# led3.net
KiCad netlist of a schematic drawn in EAGLE
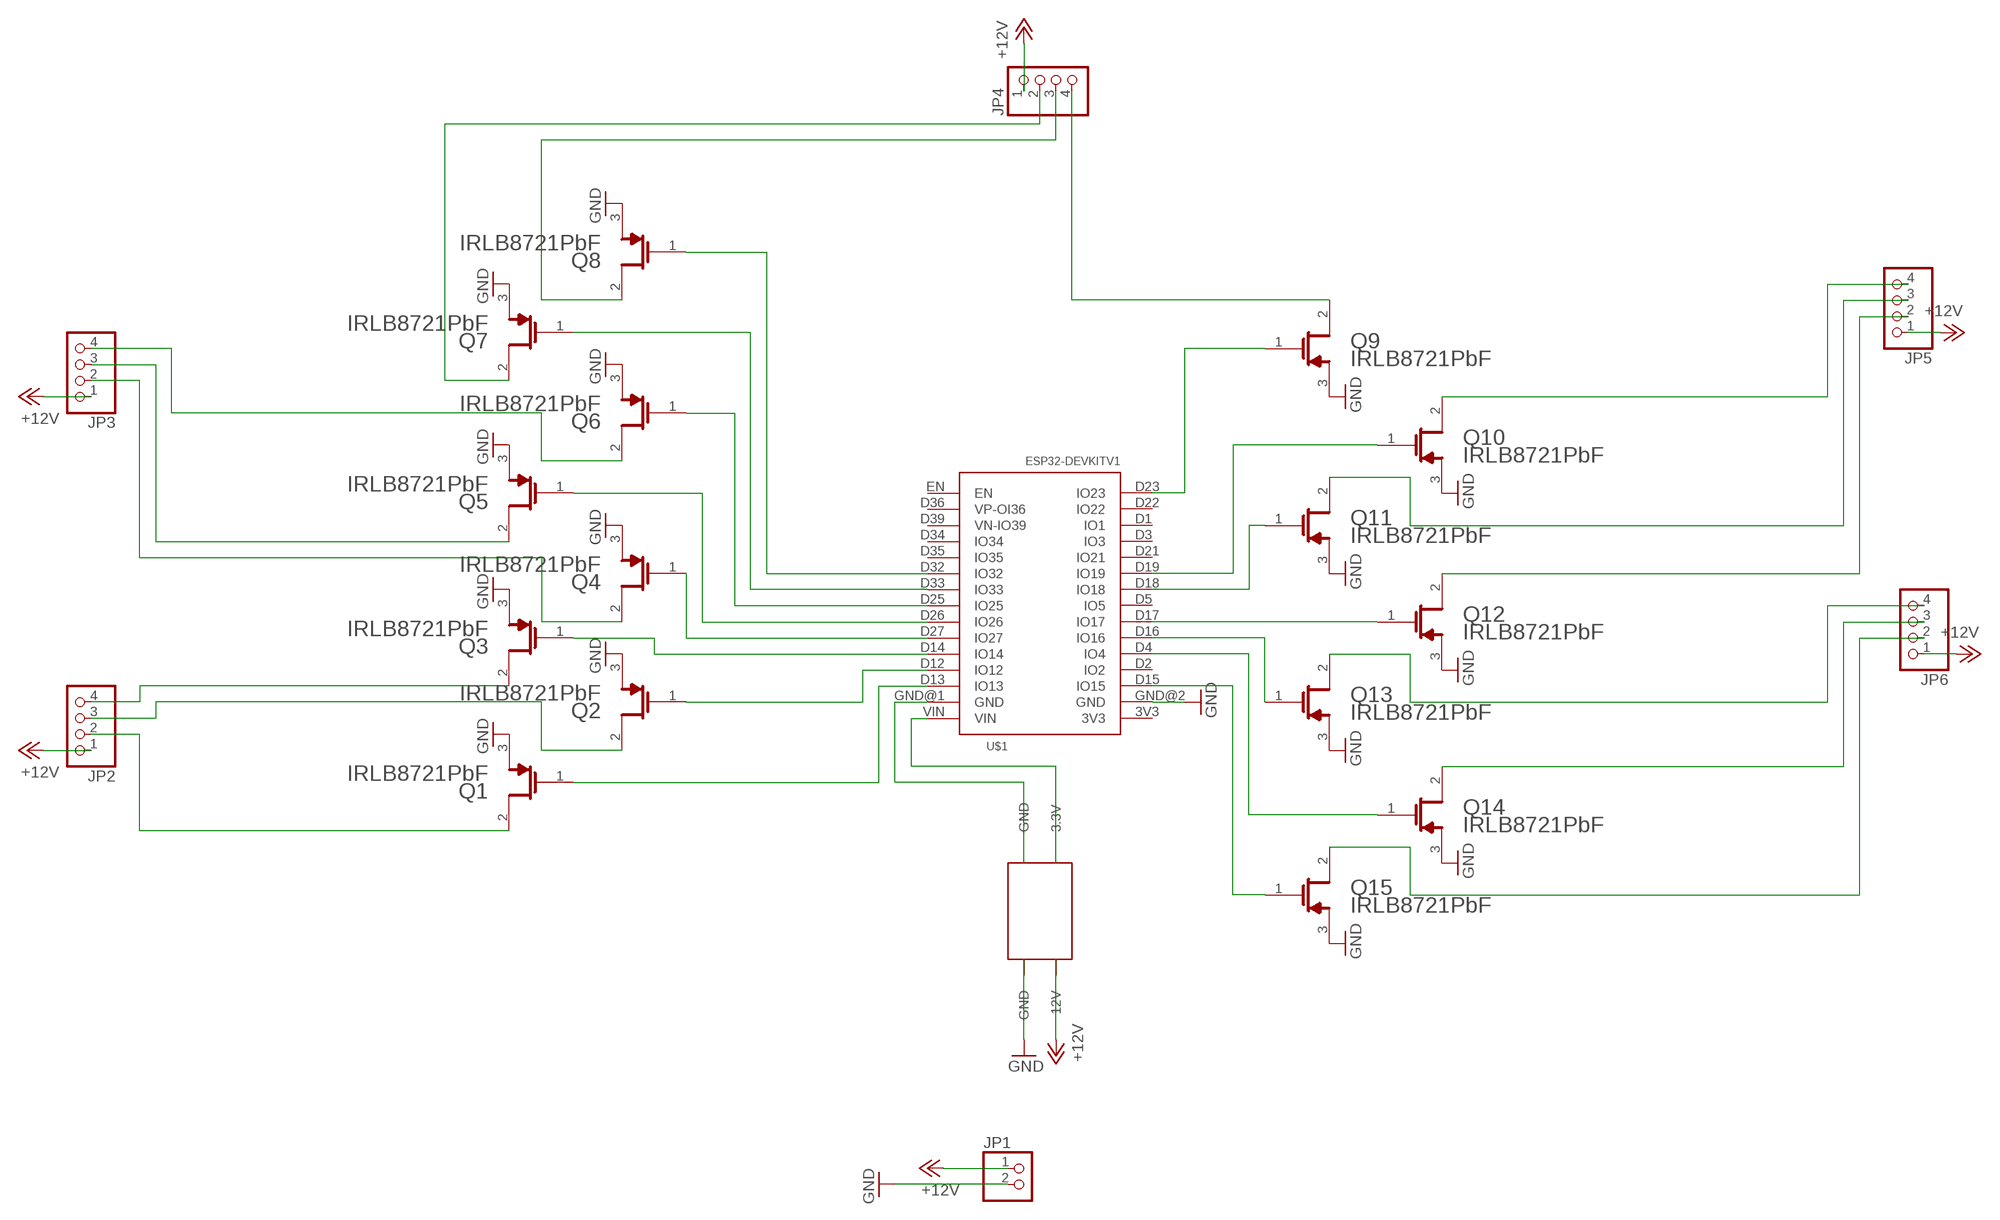
[diagram p0: schematic, sheet 1]

(export (version "E")
  (design (tool "Eeschema 10.0.6"))
  (components
    (comp (ref "JP1")
      (value "PINHD-1X2")
      (footprint "eagle-import:1X02")
      (libsource (lib "eagle-import") (part "PINHD-1X2"))
    )
    (comp (ref "JP2")
      (value "PINHD-1X4")
      (footprint "eagle-import:1X04")
      (libsource (lib "eagle-import") (part "PINHD-1X4"))
    )
    (comp (ref "JP3")
      (value "PINHD-1X4")
      (footprint "eagle-import:1X04")
      (libsource (lib "eagle-import") (part "PINHD-1X4"))
    )
    (comp (ref "JP4")
      (value "PINHD-1X4")
      (footprint "eagle-import:1X04")
      (libsource (lib "eagle-import") (part "PINHD-1X4"))
    )
    (comp (ref "JP5")
      (value "PINHD-1X4")
      (footprint "eagle-import:1X04")
      (libsource (lib "eagle-import") (part "PINHD-1X4"))
    )
    (comp (ref "JP6")
      (value "PINHD-1X4")
      (footprint "eagle-import:1X04")
      (libsource (lib "eagle-import") (part "PINHD-1X4"))
    )
    (comp (ref "Q1")
      (value "INFINEON_IRLB8721PBFINFINEON_IRLB8721PBF_0_0")
      (footprint "eagle-import:INFINEON_IRLB8721PBF_0")
      (fields
        (field (name "DIGIKEY_PART_NUMBER") "IRLB8721PBF-ND")
        (field (name "MF") "Infineon")
        (field (name "MOUSER_PART_NUMBER") "942-IRLB8721PBF")
      )
      (libsource (lib "eagle-import") (part "INFINEON_IRLB8721PBFINFINEON_IRLB8721PBF_0_0"))
    )
    (comp (ref "Q2")
      (value "INFINEON_IRLB8721PBFINFINEON_IRLB8721PBF_0_0")
      (footprint "eagle-import:INFINEON_IRLB8721PBF_0")
      (fields
        (field (name "DIGIKEY_PART_NUMBER") "IRLB8721PBF-ND")
        (field (name "MF") "Infineon")
        (field (name "MOUSER_PART_NUMBER") "942-IRLB8721PBF")
      )
      (libsource (lib "eagle-import") (part "INFINEON_IRLB8721PBFINFINEON_IRLB8721PBF_0_0"))
    )
    (comp (ref "Q3")
      (value "INFINEON_IRLB8721PBFINFINEON_IRLB8721PBF_0_0")
      (footprint "eagle-import:INFINEON_IRLB8721PBF_0")
      (fields
        (field (name "DIGIKEY_PART_NUMBER") "IRLB8721PBF-ND")
        (field (name "MF") "Infineon")
        (field (name "MOUSER_PART_NUMBER") "942-IRLB8721PBF")
      )
      (libsource (lib "eagle-import") (part "INFINEON_IRLB8721PBFINFINEON_IRLB8721PBF_0_0"))
    )
    (comp (ref "Q4")
      (value "INFINEON_IRLB8721PBFINFINEON_IRLB8721PBF_0_0")
      (footprint "eagle-import:INFINEON_IRLB8721PBF_0")
      (fields
        (field (name "DIGIKEY_PART_NUMBER") "IRLB8721PBF-ND")
        (field (name "MF") "Infineon")
        (field (name "MOUSER_PART_NUMBER") "942-IRLB8721PBF")
      )
      (libsource (lib "eagle-import") (part "INFINEON_IRLB8721PBFINFINEON_IRLB8721PBF_0_0"))
    )
    (comp (ref "Q5")
      (value "INFINEON_IRLB8721PBFINFINEON_IRLB8721PBF_0_0")
      (footprint "eagle-import:INFINEON_IRLB8721PBF_0")
      (fields
        (field (name "DIGIKEY_PART_NUMBER") "IRLB8721PBF-ND")
        (field (name "MF") "Infineon")
        (field (name "MOUSER_PART_NUMBER") "942-IRLB8721PBF")
      )
      (libsource (lib "eagle-import") (part "INFINEON_IRLB8721PBFINFINEON_IRLB8721PBF_0_0"))
    )
    (comp (ref "Q6")
      (value "INFINEON_IRLB8721PBFINFINEON_IRLB8721PBF_0_0")
      (footprint "eagle-import:INFINEON_IRLB8721PBF_0")
      (fields
        (field (name "DIGIKEY_PART_NUMBER") "IRLB8721PBF-ND")
        (field (name "MF") "Infineon")
        (field (name "MOUSER_PART_NUMBER") "942-IRLB8721PBF")
      )
      (libsource (lib "eagle-import") (part "INFINEON_IRLB8721PBFINFINEON_IRLB8721PBF_0_0"))
    )
    (comp (ref "Q7")
      (value "INFINEON_IRLB8721PBFINFINEON_IRLB8721PBF_0_0")
      (footprint "eagle-import:INFINEON_IRLB8721PBF_0")
      (fields
        (field (name "DIGIKEY_PART_NUMBER") "IRLB8721PBF-ND")
        (field (name "MF") "Infineon")
        (field (name "MOUSER_PART_NUMBER") "942-IRLB8721PBF")
      )
      (libsource (lib "eagle-import") (part "INFINEON_IRLB8721PBFINFINEON_IRLB8721PBF_0_0"))
    )
    (comp (ref "Q8")
      (value "INFINEON_IRLB8721PBFINFINEON_IRLB8721PBF_0_0")
      (footprint "eagle-import:INFINEON_IRLB8721PBF_0")
      (fields
        (field (name "DIGIKEY_PART_NUMBER") "IRLB8721PBF-ND")
        (field (name "MF") "Infineon")
        (field (name "MOUSER_PART_NUMBER") "942-IRLB8721PBF")
      )
      (libsource (lib "eagle-import") (part "INFINEON_IRLB8721PBFINFINEON_IRLB8721PBF_0_0"))
    )
    (comp (ref "Q9")
      (value "INFINEON_IRLB8721PBFINFINEON_IRLB8721PBF_0_0")
      (footprint "eagle-import:INFINEON_IRLB8721PBF_0")
      (fields
        (field (name "DIGIKEY_PART_NUMBER") "IRLB8721PBF-ND")
        (field (name "MF") "Infineon")
        (field (name "MOUSER_PART_NUMBER") "942-IRLB8721PBF")
      )
      (libsource (lib "eagle-import") (part "INFINEON_IRLB8721PBFINFINEON_IRLB8721PBF_0_0"))
    )
    (comp (ref "Q10")
      (value "INFINEON_IRLB8721PBFINFINEON_IRLB8721PBF_0_0")
      (footprint "eagle-import:INFINEON_IRLB8721PBF_0")
      (fields
        (field (name "DIGIKEY_PART_NUMBER") "IRLB8721PBF-ND")
        (field (name "MF") "Infineon")
        (field (name "MOUSER_PART_NUMBER") "942-IRLB8721PBF")
      )
      (libsource (lib "eagle-import") (part "INFINEON_IRLB8721PBFINFINEON_IRLB8721PBF_0_0"))
    )
    (comp (ref "Q11")
      (value "INFINEON_IRLB8721PBFINFINEON_IRLB8721PBF_0_0")
      (footprint "eagle-import:INFINEON_IRLB8721PBF_0")
      (fields
        (field (name "DIGIKEY_PART_NUMBER") "IRLB8721PBF-ND")
        (field (name "MF") "Infineon")
        (field (name "MOUSER_PART_NUMBER") "942-IRLB8721PBF")
      )
      (libsource (lib "eagle-import") (part "INFINEON_IRLB8721PBFINFINEON_IRLB8721PBF_0_0"))
    )
    (comp (ref "Q12")
      (value "INFINEON_IRLB8721PBFINFINEON_IRLB8721PBF_0_0")
      (footprint "eagle-import:INFINEON_IRLB8721PBF_0")
      (fields
        (field (name "DIGIKEY_PART_NUMBER") "IRLB8721PBF-ND")
        (field (name "MF") "Infineon")
        (field (name "MOUSER_PART_NUMBER") "942-IRLB8721PBF")
      )
      (libsource (lib "eagle-import") (part "INFINEON_IRLB8721PBFINFINEON_IRLB8721PBF_0_0"))
    )
    (comp (ref "Q13")
      (value "INFINEON_IRLB8721PBFINFINEON_IRLB8721PBF_0_0")
      (footprint "eagle-import:INFINEON_IRLB8721PBF_0")
      (fields
        (field (name "DIGIKEY_PART_NUMBER") "IRLB8721PBF-ND")
        (field (name "MF") "Infineon")
        (field (name "MOUSER_PART_NUMBER") "942-IRLB8721PBF")
      )
      (libsource (lib "eagle-import") (part "INFINEON_IRLB8721PBFINFINEON_IRLB8721PBF_0_0"))
    )
    (comp (ref "Q14")
      (value "INFINEON_IRLB8721PBFINFINEON_IRLB8721PBF_0_0")
      (footprint "eagle-import:INFINEON_IRLB8721PBF_0")
      (fields
        (field (name "DIGIKEY_PART_NUMBER") "IRLB8721PBF-ND")
        (field (name "MF") "Infineon")
        (field (name "MOUSER_PART_NUMBER") "942-IRLB8721PBF")
      )
      (libsource (lib "eagle-import") (part "INFINEON_IRLB8721PBFINFINEON_IRLB8721PBF_0_0"))
    )
    (comp (ref "Q15")
      (value "INFINEON_IRLB8721PBFINFINEON_IRLB8721PBF_0_0")
      (footprint "eagle-import:INFINEON_IRLB8721PBF_0")
      (fields
        (field (name "DIGIKEY_PART_NUMBER") "IRLB8721PBF-ND")
        (field (name "MF") "Infineon")
        (field (name "MOUSER_PART_NUMBER") "942-IRLB8721PBF")
      )
      (libsource (lib "eagle-import") (part "INFINEON_IRLB8721PBFINFINEON_IRLB8721PBF_0_0"))
    )
    (comp (ref "U$1")
      (value "ESP32DEVKITV1")
      (footprint "eagle-import:ESP32-DEVKITV1")
      (libsource (lib "eagle-import") (part "ESP32DEVKITV1"))
    )
    (comp (ref "U$2")
      (value "MP2307-MINI-360")
      (footprint "eagle-import:MP2307-MINI-360")
      (libsource (lib "eagle-import") (part "MP2307-MINI-360"))
    )
  )
  (nets
    (net (code "1") (name "+12V") (class "Default")
      (node (ref "JP1") (pin "1") (pinfunction "1_1") (pintype "passive"))
      (node (ref "JP2") (pin "1") (pinfunction "1_1") (pintype "passive"))
      (node (ref "JP3") (pin "1") (pinfunction "1_1") (pintype "passive"))
      (node (ref "JP4") (pin "1") (pinfunction "1_1") (pintype "passive"))
      (node (ref "JP5") (pin "1") (pinfunction "1_1") (pintype "passive"))
      (node (ref "JP6") (pin "1") (pinfunction "1_1") (pintype "passive"))
      (node (ref "U$2") (pin "12VP") (pinfunction "12V_12VP") (pintype "power_in"))
    )
    (net (code "2") (name "GND") (class "Default")
      (node (ref "JP1") (pin "2") (pinfunction "2_2") (pintype "passive"))
      (node (ref "Q1") (pin "3") (pinfunction "S_3") (pintype "bidirectional"))
      (node (ref "Q10") (pin "3") (pinfunction "S_3") (pintype "bidirectional"))
      (node (ref "Q11") (pin "3") (pinfunction "S_3") (pintype "bidirectional"))
      (node (ref "Q12") (pin "3") (pinfunction "S_3") (pintype "bidirectional"))
      (node (ref "Q13") (pin "3") (pinfunction "S_3") (pintype "bidirectional"))
      (node (ref "Q14") (pin "3") (pinfunction "S_3") (pintype "bidirectional"))
      (node (ref "Q15") (pin "3") (pinfunction "S_3") (pintype "bidirectional"))
      (node (ref "Q2") (pin "3") (pinfunction "S_3") (pintype "bidirectional"))
      (node (ref "Q3") (pin "3") (pinfunction "S_3") (pintype "bidirectional"))
      (node (ref "Q4") (pin "3") (pinfunction "S_3") (pintype "bidirectional"))
      (node (ref "Q5") (pin "3") (pinfunction "S_3") (pintype "bidirectional"))
      (node (ref "Q6") (pin "3") (pinfunction "S_3") (pintype "bidirectional"))
      (node (ref "Q7") (pin "3") (pinfunction "S_3") (pintype "bidirectional"))
      (node (ref "Q8") (pin "3") (pinfunction "S_3") (pintype "bidirectional"))
      (node (ref "Q9") (pin "3") (pinfunction "S_3") (pintype "bidirectional"))
      (node (ref "U$1") (pin "GND@2") (pinfunction "GND_GND@2") (pintype "bidirectional"))
      (node (ref "U$2") (pin "GND@1P") (pinfunction "GND_GND@1P") (pintype "power_in"))
    )
    (net (code "3") (name "Net-(Q1-D)") (class "Default")
      (node (ref "JP2") (pin "2") (pinfunction "2_2") (pintype "passive"))
      (node (ref "Q1") (pin "2") (pinfunction "D_2") (pintype "bidirectional"))
    )
    (net (code "4") (name "Net-(Q1-G)") (class "Default")
      (node (ref "Q1") (pin "1") (pinfunction "G_1") (pintype "bidirectional"))
      (node (ref "U$1") (pin "D13") (pinfunction "IO13_D13") (pintype "bidirectional"))
    )
    (net (code "5") (name "Net-(Q2-D)") (class "Default")
      (node (ref "JP2") (pin "3") (pinfunction "3_3") (pintype "passive"))
      (node (ref "Q2") (pin "2") (pinfunction "D_2") (pintype "bidirectional"))
    )
    (net (code "6") (name "Net-(Q2-G)") (class "Default")
      (node (ref "Q2") (pin "1") (pinfunction "G_1") (pintype "bidirectional"))
      (node (ref "U$1") (pin "D12") (pinfunction "IO12_D12") (pintype "bidirectional"))
    )
    (net (code "7") (name "Net-(Q3-D)") (class "Default")
      (node (ref "JP2") (pin "4") (pinfunction "4_4") (pintype "passive"))
      (node (ref "Q3") (pin "2") (pinfunction "D_2") (pintype "bidirectional"))
    )
    (net (code "8") (name "Net-(Q3-G)") (class "Default")
      (node (ref "Q3") (pin "1") (pinfunction "G_1") (pintype "bidirectional"))
      (node (ref "U$1") (pin "D14") (pinfunction "IO14_D14") (pintype "bidirectional"))
    )
    (net (code "9") (name "Net-(Q4-D)") (class "Default")
      (node (ref "JP3") (pin "2") (pinfunction "2_2") (pintype "passive"))
      (node (ref "Q4") (pin "2") (pinfunction "D_2") (pintype "bidirectional"))
    )
    (net (code "10") (name "Net-(Q4-G)") (class "Default")
      (node (ref "Q4") (pin "1") (pinfunction "G_1") (pintype "bidirectional"))
      (node (ref "U$1") (pin "D27") (pinfunction "IO27_D27") (pintype "bidirectional"))
    )
    (net (code "11") (name "Net-(Q5-D)") (class "Default")
      (node (ref "JP3") (pin "3") (pinfunction "3_3") (pintype "passive"))
      (node (ref "Q5") (pin "2") (pinfunction "D_2") (pintype "bidirectional"))
    )
    (net (code "12") (name "Net-(Q5-G)") (class "Default")
      (node (ref "Q5") (pin "1") (pinfunction "G_1") (pintype "bidirectional"))
      (node (ref "U$1") (pin "D26") (pinfunction "IO26_D26") (pintype "bidirectional"))
    )
    (net (code "13") (name "Net-(Q6-D)") (class "Default")
      (node (ref "JP3") (pin "4") (pinfunction "4_4") (pintype "passive"))
      (node (ref "Q6") (pin "2") (pinfunction "D_2") (pintype "bidirectional"))
    )
    (net (code "14") (name "Net-(Q6-G)") (class "Default")
      (node (ref "Q6") (pin "1") (pinfunction "G_1") (pintype "bidirectional"))
      (node (ref "U$1") (pin "D25") (pinfunction "IO25_D25") (pintype "bidirectional"))
    )
    (net (code "15") (name "Net-(Q7-D)") (class "Default")
      (node (ref "JP4") (pin "2") (pinfunction "2_2") (pintype "passive"))
      (node (ref "Q7") (pin "2") (pinfunction "D_2") (pintype "bidirectional"))
    )
    (net (code "16") (name "Net-(Q7-G)") (class "Default")
      (node (ref "Q7") (pin "1") (pinfunction "G_1") (pintype "bidirectional"))
      (node (ref "U$1") (pin "D33") (pinfunction "IO33_D33") (pintype "bidirectional"))
    )
    (net (code "17") (name "Net-(Q8-D)") (class "Default")
      (node (ref "JP4") (pin "3") (pinfunction "3_3") (pintype "passive"))
      (node (ref "Q8") (pin "2") (pinfunction "D_2") (pintype "bidirectional"))
    )
    (net (code "18") (name "Net-(Q8-G)") (class "Default")
      (node (ref "Q8") (pin "1") (pinfunction "G_1") (pintype "bidirectional"))
      (node (ref "U$1") (pin "D32") (pinfunction "IO32_D32") (pintype "bidirectional"))
    )
    (net (code "19") (name "Net-(Q9-D)") (class "Default")
      (node (ref "JP4") (pin "4") (pinfunction "4_4") (pintype "passive"))
      (node (ref "Q9") (pin "2") (pinfunction "D_2") (pintype "bidirectional"))
    )
    (net (code "20") (name "Net-(Q9-G)") (class "Default")
      (node (ref "Q9") (pin "1") (pinfunction "G_1") (pintype "bidirectional"))
      (node (ref "U$1") (pin "D23") (pinfunction "IO23_D23") (pintype "bidirectional"))
    )
    (net (code "21") (name "Net-(Q10-D)") (class "Default")
      (node (ref "JP5") (pin "4") (pinfunction "4_4") (pintype "passive"))
      (node (ref "Q10") (pin "2") (pinfunction "D_2") (pintype "bidirectional"))
    )
    (net (code "22") (name "Net-(Q10-G)") (class "Default")
      (node (ref "Q10") (pin "1") (pinfunction "G_1") (pintype "bidirectional"))
      (node (ref "U$1") (pin "D19") (pinfunction "IO19_D19") (pintype "bidirectional"))
    )
    (net (code "23") (name "Net-(Q11-D)") (class "Default")
      (node (ref "JP5") (pin "3") (pinfunction "3_3") (pintype "passive"))
      (node (ref "Q11") (pin "2") (pinfunction "D_2") (pintype "bidirectional"))
    )
    (net (code "24") (name "Net-(Q11-G)") (class "Default")
      (node (ref "Q11") (pin "1") (pinfunction "G_1") (pintype "bidirectional"))
      (node (ref "U$1") (pin "D18") (pinfunction "IO18_D18") (pintype "bidirectional"))
    )
    (net (code "25") (name "Net-(Q12-D)") (class "Default")
      (node (ref "JP5") (pin "2") (pinfunction "2_2") (pintype "passive"))
      (node (ref "Q12") (pin "2") (pinfunction "D_2") (pintype "bidirectional"))
    )
    (net (code "26") (name "Net-(Q12-G)") (class "Default")
      (node (ref "Q12") (pin "1") (pinfunction "G_1") (pintype "bidirectional"))
      (node (ref "U$1") (pin "D17") (pinfunction "IO17_D17") (pintype "bidirectional"))
    )
    (net (code "27") (name "Net-(Q13-D)") (class "Default")
      (node (ref "JP6") (pin "4") (pinfunction "4_4") (pintype "passive"))
      (node (ref "Q13") (pin "2") (pinfunction "D_2") (pintype "bidirectional"))
    )
    (net (code "28") (name "Net-(Q13-G)") (class "Default")
      (node (ref "Q13") (pin "1") (pinfunction "G_1") (pintype "bidirectional"))
      (node (ref "U$1") (pin "D16") (pinfunction "IO16_D16") (pintype "bidirectional"))
    )
    (net (code "29") (name "Net-(Q14-D)") (class "Default")
      (node (ref "JP6") (pin "3") (pinfunction "3_3") (pintype "passive"))
      (node (ref "Q14") (pin "2") (pinfunction "D_2") (pintype "bidirectional"))
    )
    (net (code "30") (name "Net-(Q14-G)") (class "Default")
      (node (ref "Q14") (pin "1") (pinfunction "G_1") (pintype "bidirectional"))
      (node (ref "U$1") (pin "D4") (pinfunction "IO4_D4") (pintype "bidirectional"))
    )
    (net (code "31") (name "Net-(Q15-D)") (class "Default")
      (node (ref "JP6") (pin "2") (pinfunction "2_2") (pintype "passive"))
      (node (ref "Q15") (pin "2") (pinfunction "D_2") (pintype "bidirectional"))
    )
    (net (code "32") (name "Net-(Q15-G)") (class "Default")
      (node (ref "Q15") (pin "1") (pinfunction "G_1") (pintype "bidirectional"))
      (node (ref "U$1") (pin "D15") (pinfunction "IO15_D15") (pintype "bidirectional"))
    )
    (net (code "33") (name "Net-(U$1-GND-PadGND@1)") (class "Default")
      (node (ref "U$1") (pin "GND@1") (pinfunction "GND_GND@1") (pintype "bidirectional"))
      (node (ref "U$2") (pin "GND@2P") (pinfunction "GND_GND@2P") (pintype "power_in"))
    )
    (net (code "34") (name "Net-(U$2-3.3V)") (class "Default")
      (node (ref "U$1") (pin "VIN") (pinfunction "VIN_VIN") (pintype "bidirectional"))
      (node (ref "U$2") (pin "3.3VP") (pinfunction "3.3V_3.3VP") (pintype "power_in"))
    )
    (net (code "35") (name "unconnected-(U$1-IO1-PadD1)") (class "Default")
      (node (ref "U$1") (pin "D1") (pinfunction "IO1_D1") (pintype "bidirectional"))
    )
    (net (code "36") (name "unconnected-(U$1-IO2-PadD2)") (class "Default")
      (node (ref "U$1") (pin "D2") (pinfunction "IO2_D2") (pintype "bidirectional"))
    )
    (net (code "37") (name "unconnected-(U$1-IO3-PadD3)") (class "Default")
      (node (ref "U$1") (pin "D3") (pinfunction "IO3_D3") (pintype "bidirectional"))
    )
    (net (code "38") (name "unconnected-(U$1-IO5-PadD5)") (class "Default")
      (node (ref "U$1") (pin "D5") (pinfunction "IO5_D5") (pintype "bidirectional"))
    )
    (net (code "39") (name "unconnected-(U$1-IO21-PadD21)") (class "Default")
      (node (ref "U$1") (pin "D21") (pinfunction "IO21_D21") (pintype "bidirectional"))
    )
    (net (code "40") (name "unconnected-(U$1-IO22-PadD22)") (class "Default")
      (node (ref "U$1") (pin "D22") (pinfunction "IO22_D22") (pintype "bidirectional"))
    )
    (net (code "41") (name "unconnected-(U$1-IO34-PadD34)") (class "Default")
      (node (ref "U$1") (pin "D34") (pinfunction "IO34_D34") (pintype "bidirectional"))
    )
    (net (code "42") (name "unconnected-(U$1-IO35-PadD35)") (class "Default")
      (node (ref "U$1") (pin "D35") (pinfunction "IO35_D35") (pintype "bidirectional"))
    )
    (net (code "43") (name "unconnected-(U$1-Pad3V3)") (class "Default")
      (node (ref "U$1") (pin "3V3") (pinfunction "3V3_3V3") (pintype "bidirectional"))
    )
    (net (code "44") (name "unconnected-(U$1-PadEN)") (class "Default")
      (node (ref "U$1") (pin "EN") (pinfunction "EN_EN") (pintype "bidirectional"))
    )
    (net (code "45") (name "unconnected-(U$1-VN-IO39-PadD39)") (class "Default")
      (node (ref "U$1") (pin "D39") (pinfunction "VN-IO39_D39") (pintype "bidirectional"))
    )
    (net (code "46") (name "unconnected-(U$1-VP-OI36-PadD36)") (class "Default")
      (node (ref "U$1") (pin "D36") (pinfunction "VP-OI36_D36") (pintype "bidirectional"))
    )
  )
)
